# backplane.net
KiCad netlist of a schematic drawn in Altium Designer
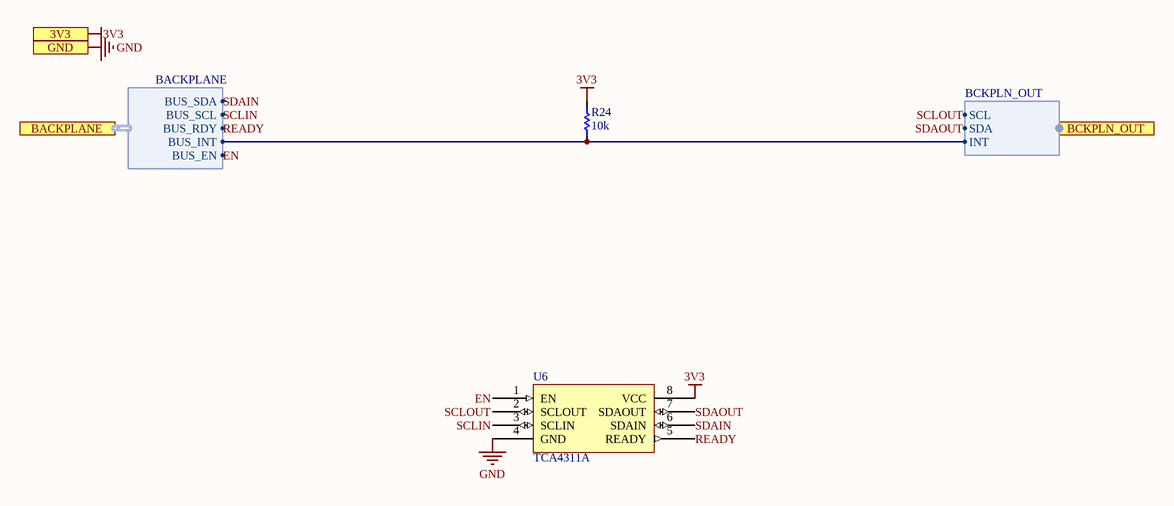
[diagram p0: backplane.SchDoc]

(export (version "E")
  (design (tool "Eeschema 10.0.6"))
  (components
    (comp (ref "R24")
      (value "10k")
      (footprint "RES 0603 L")
      (description "RES 0603")
      (libsource (lib "streetbot") (part "RES 0603"))
    )
    (comp (ref "U6")
      (value "TCA4311A")
      (footprint "SSOP-8")
      (libsource (lib "streetbot") (part "IC I2C HOTSWAP BUF"))
    )
  )
  (nets
    (net (code "3") (name "/BUS_INT") (class "Default")
      (node (ref "R24") (pin "1") (pinfunction "1_1") (pintype "passive"))
    )
    (net (code "4") (name "/EN") (class "Default")
      (node (ref "U6") (pin "1") (pinfunction "EN_1") (pintype "input"))
    )
    (net (code "5") (name "/READY") (class "Default")
      (node (ref "U6") (pin "5") (pinfunction "READY_5") (pintype "output"))
    )
    (net (code "6") (name "/SCLIN") (class "Default")
      (node (ref "U6") (pin "3") (pinfunction "SCLIN_3") (pintype "bidirectional"))
    )
    (net (code "7") (name "/SCLOUT") (class "Default")
      (node (ref "U6") (pin "2") (pinfunction "SCLOUT_2") (pintype "bidirectional"))
    )
    (net (code "8") (name "/SDAIN") (class "Default")
      (node (ref "U6") (pin "6") (pinfunction "SDAIN_6") (pintype "bidirectional"))
    )
    (net (code "9") (name "/SDAOUT") (class "Default")
      (node (ref "U6") (pin "7") (pinfunction "SDAOUT_7") (pintype "bidirectional"))
    )
    (net (code "12") (name "3V3") (class "Default")
      (node (ref "R24") (pin "2") (pinfunction "2_2") (pintype "passive"))
      (node (ref "U6") (pin "8") (pinfunction "VCC_8") (pintype "power_in"))
    )
    (net (code "13") (name "GND") (class "Default")
      (node (ref "U6") (pin "4") (pinfunction "GND_4") (pintype "power_in"))
    )
  )
)
